# AST1044.net
KiCad netlist of a schematic drawn in EAGLE
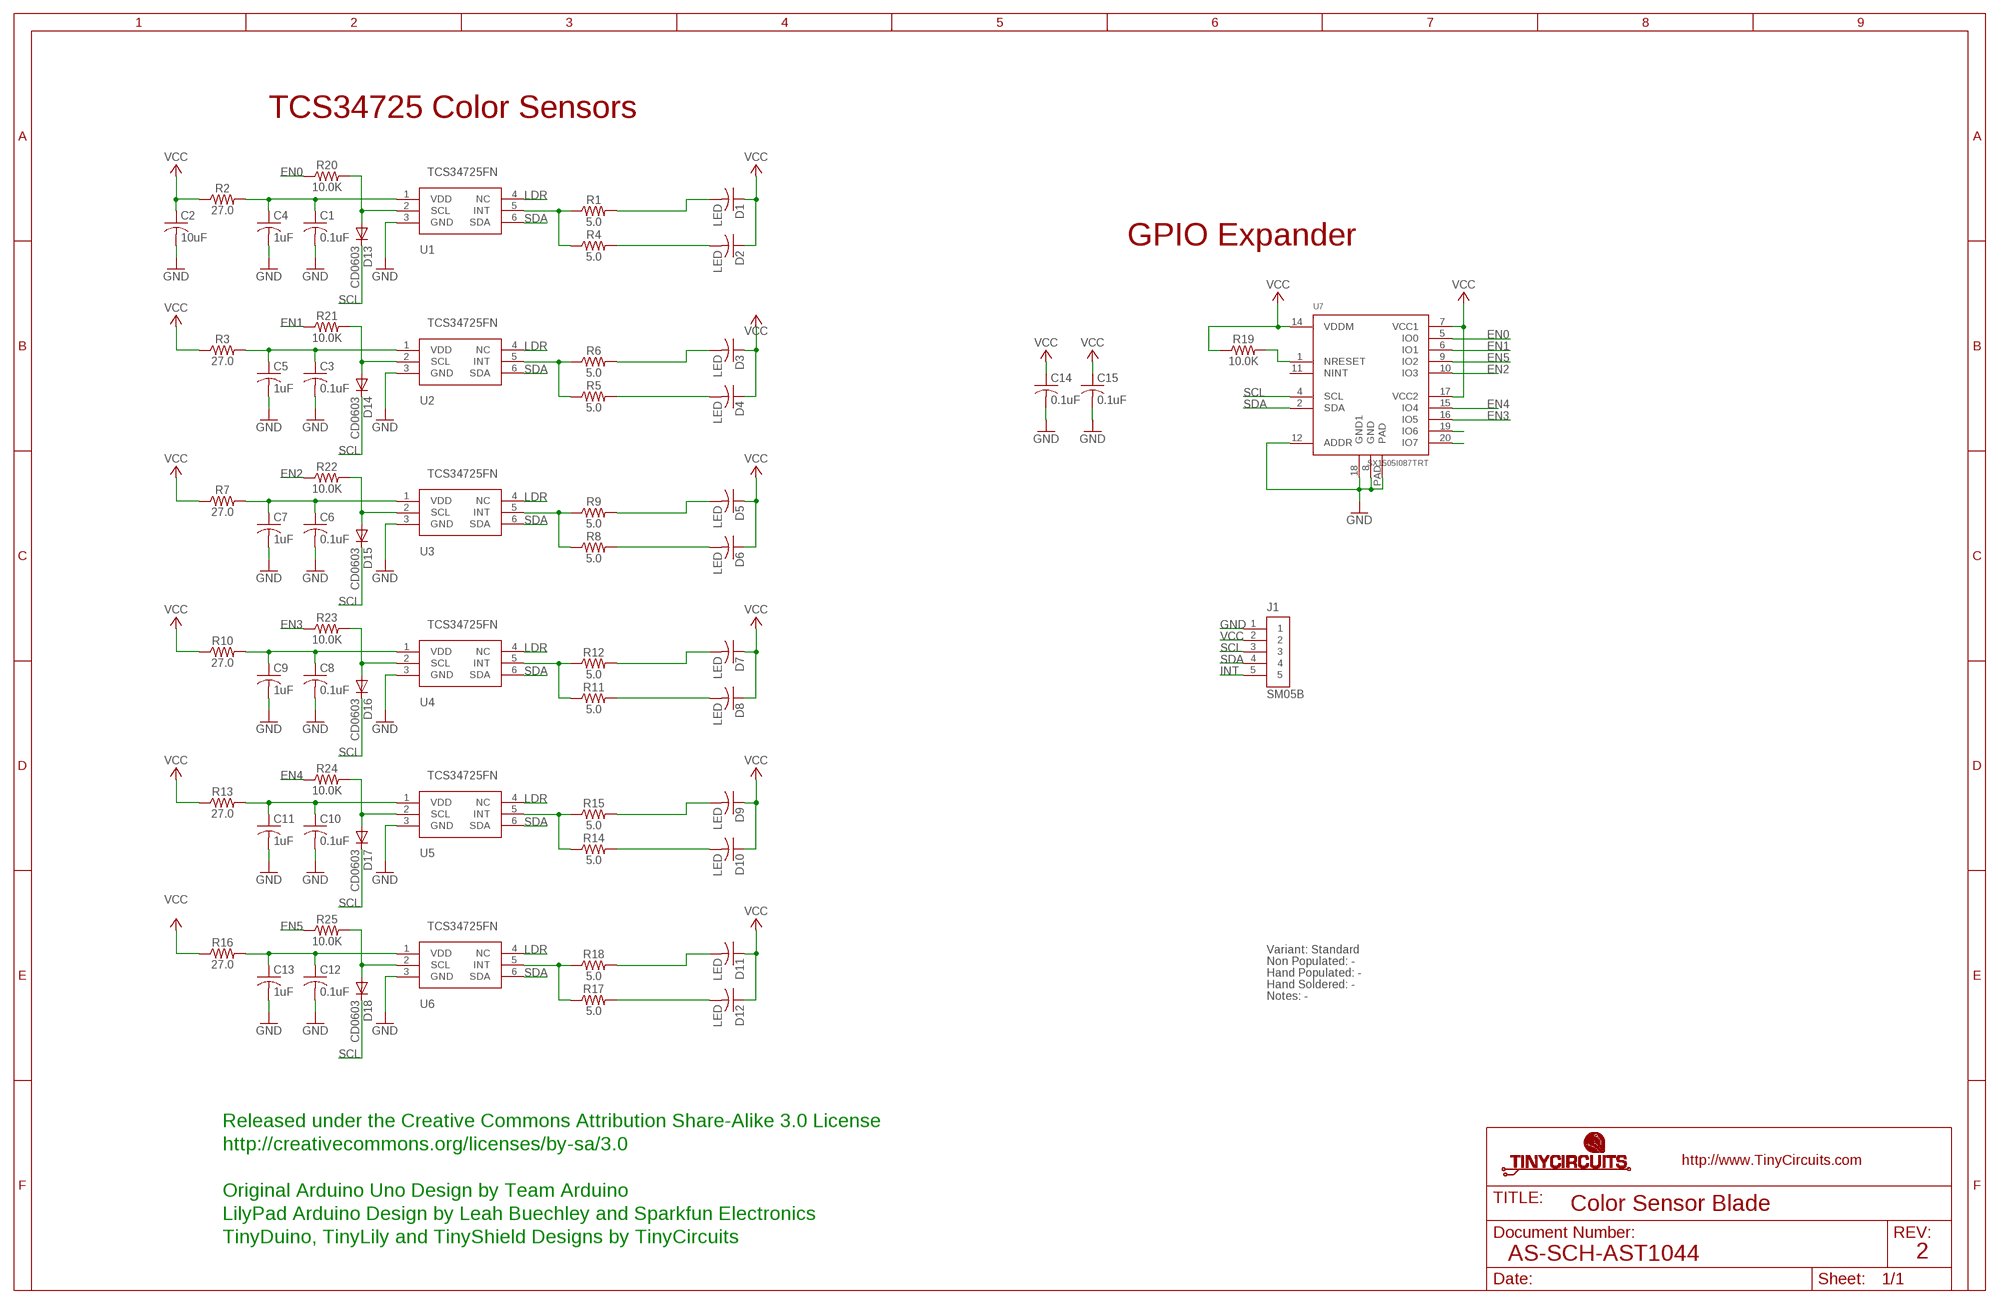
[diagram p0: schematic, sheet 1]

(export (version "E")
  (design (tool "Eeschema 10.0.6"))
  (components
    (comp (ref "C1")
      (value "0.1uF")
      (footprint "eagle-import:C0402")
      (fields (field (name "PARTNO") "AS-ITM-00008"))
      (libsource (lib "eagle-import") (part "AS-ITM-00008"))
    )
    (comp (ref "C2")
      (value "10uF")
      (footprint "eagle-import:C0603")
      (fields (field (name "PARTNO") "AS-ITM-00002"))
      (libsource (lib "eagle-import") (part "AS-ITM-00002"))
    )
    (comp (ref "C3")
      (value "0.1uF")
      (footprint "eagle-import:C0402")
      (fields (field (name "PARTNO") "AS-ITM-00008"))
      (libsource (lib "eagle-import") (part "AS-ITM-00008"))
    )
    (comp (ref "C4")
      (value "1uF")
      (footprint "eagle-import:C0402")
      (fields (field (name "PARTNO") "AS-ITM-00105") (field (name "PARTNO_1") "AS-ITM-00105"))
      (libsource (lib "eagle-import") (part "AS-ITM-00105"))
    )
    (comp (ref "C5")
      (value "1uF")
      (footprint "eagle-import:C0402")
      (fields (field (name "PARTNO") "AS-ITM-00105") (field (name "PARTNO_1") "AS-ITM-00105"))
      (libsource (lib "eagle-import") (part "AS-ITM-00105"))
    )
    (comp (ref "C6")
      (value "0.1uF")
      (footprint "eagle-import:C0402")
      (fields (field (name "PARTNO") "AS-ITM-00008"))
      (libsource (lib "eagle-import") (part "AS-ITM-00008"))
    )
    (comp (ref "C7")
      (value "1uF")
      (footprint "eagle-import:C0402")
      (fields (field (name "PARTNO") "AS-ITM-00105") (field (name "PARTNO_1") "AS-ITM-00105"))
      (libsource (lib "eagle-import") (part "AS-ITM-00105"))
    )
    (comp (ref "C8")
      (value "0.1uF")
      (footprint "eagle-import:C0402")
      (fields (field (name "PARTNO") "AS-ITM-00008"))
      (libsource (lib "eagle-import") (part "AS-ITM-00008"))
    )
    (comp (ref "C9")
      (value "1uF")
      (footprint "eagle-import:C0402")
      (fields (field (name "PARTNO") "AS-ITM-00105") (field (name "PARTNO_1") "AS-ITM-00105"))
      (libsource (lib "eagle-import") (part "AS-ITM-00105"))
    )
    (comp (ref "C10")
      (value "0.1uF")
      (footprint "eagle-import:C0402")
      (fields (field (name "PARTNO") "AS-ITM-00008"))
      (libsource (lib "eagle-import") (part "AS-ITM-00008"))
    )
    (comp (ref "C11")
      (value "1uF")
      (footprint "eagle-import:C0402")
      (fields (field (name "PARTNO") "AS-ITM-00105") (field (name "PARTNO_1") "AS-ITM-00105"))
      (libsource (lib "eagle-import") (part "AS-ITM-00105"))
    )
    (comp (ref "C12")
      (value "0.1uF")
      (footprint "eagle-import:C0402")
      (fields (field (name "PARTNO") "AS-ITM-00008"))
      (libsource (lib "eagle-import") (part "AS-ITM-00008"))
    )
    (comp (ref "C13")
      (value "1uF")
      (footprint "eagle-import:C0402")
      (fields (field (name "PARTNO") "AS-ITM-00105") (field (name "PARTNO_1") "AS-ITM-00105"))
      (libsource (lib "eagle-import") (part "AS-ITM-00105"))
    )
    (comp (ref "C14")
      (value "0.1uF")
      (footprint "eagle-import:C0402")
      (fields (field (name "PARTNO") "AS-ITM-00008"))
      (libsource (lib "eagle-import") (part "AS-ITM-00008"))
    )
    (comp (ref "C15")
      (value "0.1uF")
      (footprint "eagle-import:C0402")
      (fields (field (name "PARTNO") "AS-ITM-00008"))
      (libsource (lib "eagle-import") (part "AS-ITM-00008"))
    )
    (comp (ref "D1")
      (value "LED")
      (footprint "eagle-import:C1206")
      (fields (field (name "PARTNO") "AS-ITM-00049") (field (name "PARTNO_1") "AS-ITM-00049"))
      (libsource (lib "eagle-import") (part "AS-ITM-00049"))
    )
    (comp (ref "D2")
      (value "LED")
      (footprint "eagle-import:C1206")
      (fields (field (name "PARTNO") "AS-ITM-00049") (field (name "PARTNO_1") "AS-ITM-00049"))
      (libsource (lib "eagle-import") (part "AS-ITM-00049"))
    )
    (comp (ref "D3")
      (value "LED")
      (footprint "eagle-import:C1206")
      (fields (field (name "PARTNO") "AS-ITM-00049") (field (name "PARTNO_1") "AS-ITM-00049"))
      (libsource (lib "eagle-import") (part "AS-ITM-00049"))
    )
    (comp (ref "D4")
      (value "LED")
      (footprint "eagle-import:C1206")
      (fields (field (name "PARTNO") "AS-ITM-00049") (field (name "PARTNO_1") "AS-ITM-00049"))
      (libsource (lib "eagle-import") (part "AS-ITM-00049"))
    )
    (comp (ref "D5")
      (value "LED")
      (footprint "eagle-import:C1206")
      (fields (field (name "PARTNO") "AS-ITM-00049") (field (name "PARTNO_1") "AS-ITM-00049"))
      (libsource (lib "eagle-import") (part "AS-ITM-00049"))
    )
    (comp (ref "D6")
      (value "LED")
      (footprint "eagle-import:C1206")
      (fields (field (name "PARTNO") "AS-ITM-00049") (field (name "PARTNO_1") "AS-ITM-00049"))
      (libsource (lib "eagle-import") (part "AS-ITM-00049"))
    )
    (comp (ref "D7")
      (value "LED")
      (footprint "eagle-import:C1206")
      (fields (field (name "PARTNO") "AS-ITM-00049") (field (name "PARTNO_1") "AS-ITM-00049"))
      (libsource (lib "eagle-import") (part "AS-ITM-00049"))
    )
    (comp (ref "D8")
      (value "LED")
      (footprint "eagle-import:C1206")
      (fields (field (name "PARTNO") "AS-ITM-00049") (field (name "PARTNO_1") "AS-ITM-00049"))
      (libsource (lib "eagle-import") (part "AS-ITM-00049"))
    )
    (comp (ref "D9")
      (value "LED")
      (footprint "eagle-import:C1206")
      (fields (field (name "PARTNO") "AS-ITM-00049") (field (name "PARTNO_1") "AS-ITM-00049"))
      (libsource (lib "eagle-import") (part "AS-ITM-00049"))
    )
    (comp (ref "D10")
      (value "LED")
      (footprint "eagle-import:C1206")
      (fields (field (name "PARTNO") "AS-ITM-00049") (field (name "PARTNO_1") "AS-ITM-00049"))
      (libsource (lib "eagle-import") (part "AS-ITM-00049"))
    )
    (comp (ref "D11")
      (value "LED")
      (footprint "eagle-import:C1206")
      (fields (field (name "PARTNO") "AS-ITM-00049") (field (name "PARTNO_1") "AS-ITM-00049"))
      (libsource (lib "eagle-import") (part "AS-ITM-00049"))
    )
    (comp (ref "D12")
      (value "LED")
      (footprint "eagle-import:C1206")
      (fields (field (name "PARTNO") "AS-ITM-00049") (field (name "PARTNO_1") "AS-ITM-00049"))
      (libsource (lib "eagle-import") (part "AS-ITM-00049"))
    )
    (comp (ref "D13")
      (value "CD0603")
      (footprint "eagle-import:0603")
      (fields (field (name "PARTNO") "AS-ITM-00009"))
      (libsource (lib "eagle-import") (part "AS-ITM-00009"))
    )
    (comp (ref "D14")
      (value "CD0603")
      (footprint "eagle-import:0603")
      (fields (field (name "PARTNO") "AS-ITM-00009"))
      (libsource (lib "eagle-import") (part "AS-ITM-00009"))
    )
    (comp (ref "D15")
      (value "CD0603")
      (footprint "eagle-import:0603")
      (fields (field (name "PARTNO") "AS-ITM-00009"))
      (libsource (lib "eagle-import") (part "AS-ITM-00009"))
    )
    (comp (ref "D16")
      (value "CD0603")
      (footprint "eagle-import:0603")
      (fields (field (name "PARTNO") "AS-ITM-00009"))
      (libsource (lib "eagle-import") (part "AS-ITM-00009"))
    )
    (comp (ref "D17")
      (value "CD0603")
      (footprint "eagle-import:0603")
      (fields (field (name "PARTNO") "AS-ITM-00009"))
      (libsource (lib "eagle-import") (part "AS-ITM-00009"))
    )
    (comp (ref "D18")
      (value "CD0603")
      (footprint "eagle-import:0603")
      (fields (field (name "PARTNO") "AS-ITM-00009"))
      (libsource (lib "eagle-import") (part "AS-ITM-00009"))
    )
    (comp (ref "J1")
      (value "SM05B")
      (footprint "eagle-import:JST_SH_5X1_EDGE")
      (fields (field (name "PARTNO") "AS-ITM-00340"))
      (libsource (lib "eagle-import") (part "AS-ITM-00340EDGE"))
    )
    (comp (ref "R1")
      (value "5.0")
      (footprint "eagle-import:0402")
      (fields (field (name "PARTNO") "AS-ITM-00289") (field (name "PARTNO_1") "AS-ITM-00289"))
      (libsource (lib "eagle-import") (part "AS-ITM-00289"))
    )
    (comp (ref "R2")
      (value "27.0")
      (footprint "eagle-import:0402")
      (fields (field (name "PARTNO") "AS-ITM-00240"))
      (libsource (lib "eagle-import") (part "AS-ITM-00240"))
    )
    (comp (ref "R3")
      (value "27.0")
      (footprint "eagle-import:0402")
      (fields (field (name "PARTNO") "AS-ITM-00240"))
      (libsource (lib "eagle-import") (part "AS-ITM-00240"))
    )
    (comp (ref "R4")
      (value "5.0")
      (footprint "eagle-import:0402")
      (fields (field (name "PARTNO") "AS-ITM-00289") (field (name "PARTNO_1") "AS-ITM-00289"))
      (libsource (lib "eagle-import") (part "AS-ITM-00289"))
    )
    (comp (ref "R5")
      (value "5.0")
      (footprint "eagle-import:0402")
      (fields (field (name "PARTNO") "AS-ITM-00289") (field (name "PARTNO_1") "AS-ITM-00289"))
      (libsource (lib "eagle-import") (part "AS-ITM-00289"))
    )
    (comp (ref "R6")
      (value "5.0")
      (footprint "eagle-import:0402")
      (fields (field (name "PARTNO") "AS-ITM-00289") (field (name "PARTNO_1") "AS-ITM-00289"))
      (libsource (lib "eagle-import") (part "AS-ITM-00289"))
    )
    (comp (ref "R7")
      (value "27.0")
      (footprint "eagle-import:0402")
      (fields (field (name "PARTNO") "AS-ITM-00240"))
      (libsource (lib "eagle-import") (part "AS-ITM-00240"))
    )
    (comp (ref "R8")
      (value "5.0")
      (footprint "eagle-import:0402")
      (fields (field (name "PARTNO") "AS-ITM-00289") (field (name "PARTNO_1") "AS-ITM-00289"))
      (libsource (lib "eagle-import") (part "AS-ITM-00289"))
    )
    (comp (ref "R9")
      (value "5.0")
      (footprint "eagle-import:0402")
      (fields (field (name "PARTNO") "AS-ITM-00289") (field (name "PARTNO_1") "AS-ITM-00289"))
      (libsource (lib "eagle-import") (part "AS-ITM-00289"))
    )
    (comp (ref "R10")
      (value "27.0")
      (footprint "eagle-import:0402")
      (fields (field (name "PARTNO") "AS-ITM-00240"))
      (libsource (lib "eagle-import") (part "AS-ITM-00240"))
    )
    (comp (ref "R11")
      (value "5.0")
      (footprint "eagle-import:0402")
      (fields (field (name "PARTNO") "AS-ITM-00289") (field (name "PARTNO_1") "AS-ITM-00289"))
      (libsource (lib "eagle-import") (part "AS-ITM-00289"))
    )
    (comp (ref "R12")
      (value "5.0")
      (footprint "eagle-import:0402")
      (fields (field (name "PARTNO") "AS-ITM-00289") (field (name "PARTNO_1") "AS-ITM-00289"))
      (libsource (lib "eagle-import") (part "AS-ITM-00289"))
    )
    (comp (ref "R13")
      (value "27.0")
      (footprint "eagle-import:0402")
      (fields (field (name "PARTNO") "AS-ITM-00240"))
      (libsource (lib "eagle-import") (part "AS-ITM-00240"))
    )
    (comp (ref "R14")
      (value "5.0")
      (footprint "eagle-import:0402")
      (fields (field (name "PARTNO") "AS-ITM-00289") (field (name "PARTNO_1") "AS-ITM-00289"))
      (libsource (lib "eagle-import") (part "AS-ITM-00289"))
    )
    (comp (ref "R15")
      (value "5.0")
      (footprint "eagle-import:0402")
      (fields (field (name "PARTNO") "AS-ITM-00289") (field (name "PARTNO_1") "AS-ITM-00289"))
      (libsource (lib "eagle-import") (part "AS-ITM-00289"))
    )
    (comp (ref "R16")
      (value "27.0")
      (footprint "eagle-import:0402")
      (fields (field (name "PARTNO") "AS-ITM-00240"))
      (libsource (lib "eagle-import") (part "AS-ITM-00240"))
    )
    (comp (ref "R17")
      (value "5.0")
      (footprint "eagle-import:0402")
      (fields (field (name "PARTNO") "AS-ITM-00289") (field (name "PARTNO_1") "AS-ITM-00289"))
      (libsource (lib "eagle-import") (part "AS-ITM-00289"))
    )
    (comp (ref "R18")
      (value "5.0")
      (footprint "eagle-import:0402")
      (fields (field (name "PARTNO") "AS-ITM-00289") (field (name "PARTNO_1") "AS-ITM-00289"))
      (libsource (lib "eagle-import") (part "AS-ITM-00289"))
    )
    (comp (ref "R19")
      (value "10.0K")
      (footprint "eagle-import:0402")
      (fields (field (name "PARTNO") "AS-ITM-00032"))
      (libsource (lib "eagle-import") (part "AS-ITM-00032"))
    )
    (comp (ref "R20")
      (value "10.0K")
      (footprint "eagle-import:0402")
      (fields (field (name "PARTNO") "AS-ITM-00032"))
      (libsource (lib "eagle-import") (part "AS-ITM-00032"))
    )
    (comp (ref "R21")
      (value "10.0K")
      (footprint "eagle-import:0402")
      (fields (field (name "PARTNO") "AS-ITM-00032"))
      (libsource (lib "eagle-import") (part "AS-ITM-00032"))
    )
    (comp (ref "R22")
      (value "10.0K")
      (footprint "eagle-import:0402")
      (fields (field (name "PARTNO") "AS-ITM-00032"))
      (libsource (lib "eagle-import") (part "AS-ITM-00032"))
    )
    (comp (ref "R23")
      (value "10.0K")
      (footprint "eagle-import:0402")
      (fields (field (name "PARTNO") "AS-ITM-00032"))
      (libsource (lib "eagle-import") (part "AS-ITM-00032"))
    )
    (comp (ref "R24")
      (value "10.0K")
      (footprint "eagle-import:0402")
      (fields (field (name "PARTNO") "AS-ITM-00032"))
      (libsource (lib "eagle-import") (part "AS-ITM-00032"))
    )
    (comp (ref "R25")
      (value "10.0K")
      (footprint "eagle-import:0402")
      (fields (field (name "PARTNO") "AS-ITM-00032"))
      (libsource (lib "eagle-import") (part "AS-ITM-00032"))
    )
    (comp (ref "U1")
      (value "TCS34725FN")
      (footprint "eagle-import:TSL2572")
      (fields (field (name "PARTNO") "AS-ITM-00140") (field (name "PARTNO_1") "AS-ITM-00140"))
      (libsource (lib "eagle-import") (part "AS-ITM-00140"))
    )
    (comp (ref "U2")
      (value "TCS34725FN")
      (footprint "eagle-import:TSL2572")
      (fields (field (name "PARTNO") "AS-ITM-00140") (field (name "PARTNO_1") "AS-ITM-00140"))
      (libsource (lib "eagle-import") (part "AS-ITM-00140"))
    )
    (comp (ref "U3")
      (value "TCS34725FN")
      (footprint "eagle-import:TSL2572")
      (fields (field (name "PARTNO") "AS-ITM-00140") (field (name "PARTNO_1") "AS-ITM-00140"))
      (libsource (lib "eagle-import") (part "AS-ITM-00140"))
    )
    (comp (ref "U4")
      (value "TCS34725FN")
      (footprint "eagle-import:TSL2572")
      (fields (field (name "PARTNO") "AS-ITM-00140") (field (name "PARTNO_1") "AS-ITM-00140"))
      (libsource (lib "eagle-import") (part "AS-ITM-00140"))
    )
    (comp (ref "U5")
      (value "TCS34725FN")
      (footprint "eagle-import:TSL2572")
      (fields (field (name "PARTNO") "AS-ITM-00140") (field (name "PARTNO_1") "AS-ITM-00140"))
      (libsource (lib "eagle-import") (part "AS-ITM-00140"))
    )
    (comp (ref "U6")
      (value "TCS34725FN")
      (footprint "eagle-import:TSL2572")
      (fields (field (name "PARTNO") "AS-ITM-00140") (field (name "PARTNO_1") "AS-ITM-00140"))
      (libsource (lib "eagle-import") (part "AS-ITM-00140"))
    )
    (comp (ref "U7")
      (value "SX1505I087TRT")
      (footprint "eagle-import:QFN-UT20")
      (fields (field (name "PARTNO") "AS-ITM-00203"))
      (libsource (lib "eagle-import") (part "AS-ITM-00203"))
    )
  )
  (nets
    (net (code "1") (name "/EN0") (class "Default")
      (node (ref "R20") (pin "1") (pinfunction "1_1") (pintype "passive"))
      (node (ref "U7") (pin "5") (pinfunction "IO0_5") (pintype "bidirectional"))
    )
    (net (code "2") (name "/EN1") (class "Default")
      (node (ref "R21") (pin "1") (pinfunction "1_1") (pintype "passive"))
      (node (ref "U7") (pin "6") (pinfunction "IO1_6") (pintype "bidirectional"))
    )
    (net (code "3") (name "/EN2") (class "Default")
      (node (ref "R22") (pin "1") (pinfunction "1_1") (pintype "passive"))
      (node (ref "U7") (pin "10") (pinfunction "IO3_10") (pintype "bidirectional"))
    )
    (net (code "4") (name "/EN3") (class "Default")
      (node (ref "R23") (pin "1") (pinfunction "1_1") (pintype "passive"))
      (node (ref "U7") (pin "16") (pinfunction "IO5_16") (pintype "bidirectional"))
    )
    (net (code "5") (name "/EN4") (class "Default")
      (node (ref "R24") (pin "1") (pinfunction "1_1") (pintype "passive"))
      (node (ref "U7") (pin "15") (pinfunction "IO4_15") (pintype "bidirectional"))
    )
    (net (code "6") (name "/EN5") (class "Default")
      (node (ref "R25") (pin "1") (pinfunction "1_1") (pintype "passive"))
      (node (ref "U7") (pin "9") (pinfunction "IO2_9") (pintype "bidirectional"))
    )
    (net (code "7") (name "/INT") (class "Default")
      (node (ref "J1") (pin "5") (pinfunction "5_5") (pintype "bidirectional"))
    )
    (net (code "8") (name "/LDR") (class "Default")
      (node (ref "U1") (pin "4") (pinfunction "NC_4") (pintype "bidirectional"))
      (node (ref "U2") (pin "4") (pinfunction "NC_4") (pintype "bidirectional"))
      (node (ref "U3") (pin "4") (pinfunction "NC_4") (pintype "bidirectional"))
      (node (ref "U4") (pin "4") (pinfunction "NC_4") (pintype "bidirectional"))
      (node (ref "U5") (pin "4") (pinfunction "NC_4") (pintype "bidirectional"))
      (node (ref "U6") (pin "4") (pinfunction "NC_4") (pintype "bidirectional"))
    )
    (net (code "9") (name "/SCL") (class "Default")
      (node (ref "D13") (pin "C") (pinfunction "C_C") (pintype "passive"))
      (node (ref "D14") (pin "C") (pinfunction "C_C") (pintype "passive"))
      (node (ref "D15") (pin "C") (pinfunction "C_C") (pintype "passive"))
      (node (ref "D16") (pin "C") (pinfunction "C_C") (pintype "passive"))
      (node (ref "D17") (pin "C") (pinfunction "C_C") (pintype "passive"))
      (node (ref "D18") (pin "C") (pinfunction "C_C") (pintype "passive"))
      (node (ref "J1") (pin "3") (pinfunction "3_3") (pintype "bidirectional"))
      (node (ref "U7") (pin "4") (pinfunction "SCL_4") (pintype "bidirectional"))
    )
    (net (code "10") (name "/SDA") (class "Default")
      (node (ref "J1") (pin "4") (pinfunction "4_4") (pintype "bidirectional"))
      (node (ref "U1") (pin "6") (pinfunction "SDA_6") (pintype "bidirectional"))
      (node (ref "U2") (pin "6") (pinfunction "SDA_6") (pintype "bidirectional"))
      (node (ref "U3") (pin "6") (pinfunction "SDA_6") (pintype "bidirectional"))
      (node (ref "U4") (pin "6") (pinfunction "SDA_6") (pintype "bidirectional"))
      (node (ref "U5") (pin "6") (pinfunction "SDA_6") (pintype "bidirectional"))
      (node (ref "U6") (pin "6") (pinfunction "SDA_6") (pintype "bidirectional"))
      (node (ref "U7") (pin "2") (pinfunction "SDA_2") (pintype "bidirectional"))
    )
    (net (code "11") (name "GND") (class "Default")
      (node (ref "C1") (pin "2") (pinfunction "2_2") (pintype "passive"))
      (node (ref "C10") (pin "2") (pinfunction "2_2") (pintype "passive"))
      (node (ref "C11") (pin "2") (pinfunction "2_2") (pintype "passive"))
      (node (ref "C12") (pin "2") (pinfunction "2_2") (pintype "passive"))
      (node (ref "C13") (pin "2") (pinfunction "2_2") (pintype "passive"))
      (node (ref "C14") (pin "2") (pinfunction "2_2") (pintype "passive"))
      (node (ref "C15") (pin "2") (pinfunction "2_2") (pintype "passive"))
      (node (ref "C2") (pin "2") (pinfunction "2_2") (pintype "passive"))
      (node (ref "C3") (pin "2") (pinfunction "2_2") (pintype "passive"))
      (node (ref "C4") (pin "2") (pinfunction "2_2") (pintype "passive"))
      (node (ref "C5") (pin "2") (pinfunction "2_2") (pintype "passive"))
      (node (ref "C6") (pin "2") (pinfunction "2_2") (pintype "passive"))
      (node (ref "C7") (pin "2") (pinfunction "2_2") (pintype "passive"))
      (node (ref "C8") (pin "2") (pinfunction "2_2") (pintype "passive"))
      (node (ref "C9") (pin "2") (pinfunction "2_2") (pintype "passive"))
      (node (ref "J1") (pin "1") (pinfunction "1_1") (pintype "bidirectional"))
      (node (ref "U1") (pin "3") (pinfunction "GND_3") (pintype "bidirectional"))
      (node (ref "U2") (pin "3") (pinfunction "GND_3") (pintype "bidirectional"))
      (node (ref "U3") (pin "3") (pinfunction "GND_3") (pintype "bidirectional"))
      (node (ref "U4") (pin "3") (pinfunction "GND_3") (pintype "bidirectional"))
      (node (ref "U5") (pin "3") (pinfunction "GND_3") (pintype "bidirectional"))
      (node (ref "U6") (pin "3") (pinfunction "GND_3") (pintype "bidirectional"))
      (node (ref "U7") (pin "12") (pinfunction "ADDR_12") (pintype "bidirectional"))
      (node (ref "U7") (pin "18") (pinfunction "GND1_18") (pintype "bidirectional"))
      (node (ref "U7") (pin "8") (pinfunction "GND_8") (pintype "bidirectional"))
      (node (ref "U7") (pin "PAD") (pinfunction "PAD_PAD") (pintype "bidirectional"))
    )
    (net (code "12") (name "Net-(D1-Pad2)") (class "Default")
      (node (ref "D1") (pin "2") (pinfunction "2_2") (pintype "passive"))
      (node (ref "R1") (pin "2") (pinfunction "2_2") (pintype "passive"))
    )
    (net (code "13") (name "Net-(D2-Pad2)") (class "Default")
      (node (ref "D2") (pin "2") (pinfunction "2_2") (pintype "passive"))
      (node (ref "R4") (pin "2") (pinfunction "2_2") (pintype "passive"))
    )
    (net (code "14") (name "Net-(D3-Pad2)") (class "Default")
      (node (ref "D3") (pin "2") (pinfunction "2_2") (pintype "passive"))
      (node (ref "R6") (pin "2") (pinfunction "2_2") (pintype "passive"))
    )
    (net (code "15") (name "Net-(D4-Pad2)") (class "Default")
      (node (ref "D4") (pin "2") (pinfunction "2_2") (pintype "passive"))
      (node (ref "R5") (pin "2") (pinfunction "2_2") (pintype "passive"))
    )
    (net (code "16") (name "Net-(D5-Pad2)") (class "Default")
      (node (ref "D5") (pin "2") (pinfunction "2_2") (pintype "passive"))
      (node (ref "R9") (pin "2") (pinfunction "2_2") (pintype "passive"))
    )
    (net (code "17") (name "Net-(D6-Pad2)") (class "Default")
      (node (ref "D6") (pin "2") (pinfunction "2_2") (pintype "passive"))
      (node (ref "R8") (pin "2") (pinfunction "2_2") (pintype "passive"))
    )
    (net (code "18") (name "Net-(D7-Pad2)") (class "Default")
      (node (ref "D7") (pin "2") (pinfunction "2_2") (pintype "passive"))
      (node (ref "R12") (pin "2") (pinfunction "2_2") (pintype "passive"))
    )
    (net (code "19") (name "Net-(D8-Pad2)") (class "Default")
      (node (ref "D8") (pin "2") (pinfunction "2_2") (pintype "passive"))
      (node (ref "R11") (pin "2") (pinfunction "2_2") (pintype "passive"))
    )
    (net (code "20") (name "Net-(D9-Pad2)") (class "Default")
      (node (ref "D9") (pin "2") (pinfunction "2_2") (pintype "passive"))
      (node (ref "R15") (pin "2") (pinfunction "2_2") (pintype "passive"))
    )
    (net (code "21") (name "Net-(D10-Pad2)") (class "Default")
      (node (ref "D10") (pin "2") (pinfunction "2_2") (pintype "passive"))
      (node (ref "R14") (pin "2") (pinfunction "2_2") (pintype "passive"))
    )
    (net (code "22") (name "Net-(D11-Pad2)") (class "Default")
      (node (ref "D11") (pin "2") (pinfunction "2_2") (pintype "passive"))
      (node (ref "R18") (pin "2") (pinfunction "2_2") (pintype "passive"))
    )
    (net (code "23") (name "Net-(D12-Pad2)") (class "Default")
      (node (ref "D12") (pin "2") (pinfunction "2_2") (pintype "passive"))
      (node (ref "R17") (pin "2") (pinfunction "2_2") (pintype "passive"))
    )
    (net (code "24") (name "Net-(U1-INT)") (class "Default")
      (node (ref "R1") (pin "1") (pinfunction "1_1") (pintype "passive"))
      (node (ref "R4") (pin "1") (pinfunction "1_1") (pintype "passive"))
      (node (ref "U1") (pin "5") (pinfunction "INT_5") (pintype "bidirectional"))
    )
    (net (code "25") (name "Net-(U1-SCL)") (class "Default")
      (node (ref "D13") (pin "A") (pinfunction "A_A") (pintype "passive"))
      (node (ref "R20") (pin "2") (pinfunction "2_2") (pintype "passive"))
      (node (ref "U1") (pin "2") (pinfunction "SCL_2") (pintype "bidirectional"))
    )
    (net (code "26") (name "Net-(U1-VDD)") (class "Default")
      (node (ref "C1") (pin "1") (pinfunction "1_1") (pintype "passive"))
      (node (ref "C4") (pin "1") (pinfunction "1_1") (pintype "passive"))
      (node (ref "R2") (pin "2") (pinfunction "2_2") (pintype "passive"))
      (node (ref "U1") (pin "1") (pinfunction "VDD_1") (pintype "bidirectional"))
    )
    (net (code "27") (name "Net-(U2-INT)") (class "Default")
      (node (ref "R5") (pin "1") (pinfunction "1_1") (pintype "passive"))
      (node (ref "R6") (pin "1") (pinfunction "1_1") (pintype "passive"))
      (node (ref "U2") (pin "5") (pinfunction "INT_5") (pintype "bidirectional"))
    )
    (net (code "28") (name "Net-(U2-SCL)") (class "Default")
      (node (ref "D14") (pin "A") (pinfunction "A_A") (pintype "passive"))
      (node (ref "R21") (pin "2") (pinfunction "2_2") (pintype "passive"))
      (node (ref "U2") (pin "2") (pinfunction "SCL_2") (pintype "bidirectional"))
    )
    (net (code "29") (name "Net-(U2-VDD)") (class "Default")
      (node (ref "C3") (pin "1") (pinfunction "1_1") (pintype "passive"))
      (node (ref "C5") (pin "1") (pinfunction "1_1") (pintype "passive"))
      (node (ref "R3") (pin "2") (pinfunction "2_2") (pintype "passive"))
      (node (ref "U2") (pin "1") (pinfunction "VDD_1") (pintype "bidirectional"))
    )
    (net (code "30") (name "Net-(U3-INT)") (class "Default")
      (node (ref "R8") (pin "1") (pinfunction "1_1") (pintype "passive"))
      (node (ref "R9") (pin "1") (pinfunction "1_1") (pintype "passive"))
      (node (ref "U3") (pin "5") (pinfunction "INT_5") (pintype "bidirectional"))
    )
    (net (code "31") (name "Net-(U3-SCL)") (class "Default")
      (node (ref "D15") (pin "A") (pinfunction "A_A") (pintype "passive"))
      (node (ref "R22") (pin "2") (pinfunction "2_2") (pintype "passive"))
      (node (ref "U3") (pin "2") (pinfunction "SCL_2") (pintype "bidirectional"))
    )
    (net (code "32") (name "Net-(U3-VDD)") (class "Default")
      (node (ref "C6") (pin "1") (pinfunction "1_1") (pintype "passive"))
      (node (ref "C7") (pin "1") (pinfunction "1_1") (pintype "passive"))
      (node (ref "R7") (pin "2") (pinfunction "2_2") (pintype "passive"))
      (node (ref "U3") (pin "1") (pinfunction "VDD_1") (pintype "bidirectional"))
    )
    (net (code "33") (name "Net-(U4-INT)") (class "Default")
      (node (ref "R11") (pin "1") (pinfunction "1_1") (pintype "passive"))
      (node (ref "R12") (pin "1") (pinfunction "1_1") (pintype "passive"))
      (node (ref "U4") (pin "5") (pinfunction "INT_5") (pintype "bidirectional"))
    )
    (net (code "34") (name "Net-(U4-SCL)") (class "Default")
      (node (ref "D16") (pin "A") (pinfunction "A_A") (pintype "passive"))
      (node (ref "R23") (pin "2") (pinfunction "2_2") (pintype "passive"))
      (node (ref "U4") (pin "2") (pinfunction "SCL_2") (pintype "bidirectional"))
    )
    (net (code "35") (name "Net-(U4-VDD)") (class "Default")
      (node (ref "C8") (pin "1") (pinfunction "1_1") (pintype "passive"))
      (node (ref "C9") (pin "1") (pinfunction "1_1") (pintype "passive"))
      (node (ref "R10") (pin "2") (pinfunction "2_2") (pintype "passive"))
      (node (ref "U4") (pin "1") (pinfunction "VDD_1") (pintype "bidirectional"))
    )
    (net (code "36") (name "Net-(U5-INT)") (class "Default")
      (node (ref "R14") (pin "1") (pinfunction "1_1") (pintype "passive"))
      (node (ref "R15") (pin "1") (pinfunction "1_1") (pintype "passive"))
      (node (ref "U5") (pin "5") (pinfunction "INT_5") (pintype "bidirectional"))
    )
    (net (code "37") (name "Net-(U5-SCL)") (class "Default")
      (node (ref "D17") (pin "A") (pinfunction "A_A") (pintype "passive"))
      (node (ref "R24") (pin "2") (pinfunction "2_2") (pintype "passive"))
      (node (ref "U5") (pin "2") (pinfunction "SCL_2") (pintype "bidirectional"))
    )
    (net (code "38") (name "Net-(U5-VDD)") (class "Default")
      (node (ref "C10") (pin "1") (pinfunction "1_1") (pintype "passive"))
      (node (ref "C11") (pin "1") (pinfunction "1_1") (pintype "passive"))
      (node (ref "R13") (pin "2") (pinfunction "2_2") (pintype "passive"))
      (node (ref "U5") (pin "1") (pinfunction "VDD_1") (pintype "bidirectional"))
    )
    (net (code "39") (name "Net-(U6-INT)") (class "Default")
      (node (ref "R17") (pin "1") (pinfunction "1_1") (pintype "passive"))
      (node (ref "R18") (pin "1") (pinfunction "1_1") (pintype "passive"))
      (node (ref "U6") (pin "5") (pinfunction "INT_5") (pintype "bidirectional"))
    )
    (net (code "40") (name "Net-(U6-SCL)") (class "Default")
      (node (ref "D18") (pin "A") (pinfunction "A_A") (pintype "passive"))
      (node (ref "R25") (pin "2") (pinfunction "2_2") (pintype "passive"))
      (node (ref "U6") (pin "2") (pinfunction "SCL_2") (pintype "bidirectional"))
    )
    (net (code "41") (name "Net-(U6-VDD)") (class "Default")
      (node (ref "C12") (pin "1") (pinfunction "1_1") (pintype "passive"))
      (node (ref "C13") (pin "1") (pinfunction "1_1") (pintype "passive"))
      (node (ref "R16") (pin "2") (pinfunction "2_2") (pintype "passive"))
      (node (ref "U6") (pin "1") (pinfunction "VDD_1") (pintype "bidirectional"))
    )
    (net (code "42") (name "Net-(U7-NRESET)") (class "Default")
      (node (ref "R19") (pin "2") (pinfunction "2_2") (pintype "passive"))
      (node (ref "U7") (pin "1") (pinfunction "NRESET_1") (pintype "bidirectional"))
    )
    (net (code "43") (name "VCC") (class "Default")
      (node (ref "C14") (pin "1") (pinfunction "1_1") (pintype "passive"))
      (node (ref "C15") (pin "1") (pinfunction "1_1") (pintype "passive"))
      (node (ref "C2") (pin "1") (pinfunction "1_1") (pintype "passive"))
      (node (ref "D1") (pin "1") (pinfunction "1_1") (pintype "passive"))
      (node (ref "D10") (pin "1") (pinfunction "1_1") (pintype "passive"))
      (node (ref "D11") (pin "1") (pinfunction "1_1") (pintype "passive"))
      (node (ref "D12") (pin "1") (pinfunction "1_1") (pintype "passive"))
      (node (ref "D2") (pin "1") (pinfunction "1_1") (pintype "passive"))
      (node (ref "D3") (pin "1") (pinfunction "1_1") (pintype "passive"))
      (node (ref "D4") (pin "1") (pinfunction "1_1") (pintype "passive"))
      (node (ref "D5") (pin "1") (pinfunction "1_1") (pintype "passive"))
      (node (ref "D6") (pin "1") (pinfunction "1_1") (pintype "passive"))
      (node (ref "D7") (pin "1") (pinfunction "1_1") (pintype "passive"))
      (node (ref "D8") (pin "1") (pinfunction "1_1") (pintype "passive"))
      (node (ref "D9") (pin "1") (pinfunction "1_1") (pintype "passive"))
      (node (ref "J1") (pin "2") (pinfunction "2_2") (pintype "bidirectional"))
      (node (ref "R10") (pin "1") (pinfunction "1_1") (pintype "passive"))
      (node (ref "R13") (pin "1") (pinfunction "1_1") (pintype "passive"))
      (node (ref "R16") (pin "1") (pinfunction "1_1") (pintype "passive"))
      (node (ref "R19") (pin "1") (pinfunction "1_1") (pintype "passive"))
      (node (ref "R2") (pin "1") (pinfunction "1_1") (pintype "passive"))
      (node (ref "R3") (pin "1") (pinfunction "1_1") (pintype "passive"))
      (node (ref "R7") (pin "1") (pinfunction "1_1") (pintype "passive"))
      (node (ref "U7") (pin "14") (pinfunction "VDDM_14") (pintype "bidirectional"))
      (node (ref "U7") (pin "17") (pinfunction "VCC2_17") (pintype "bidirectional"))
      (node (ref "U7") (pin "7") (pinfunction "VCC1_7") (pintype "bidirectional"))
    )
    (net (code "44") (name "unconnected-(U7-IO6-Pad19)") (class "Default")
      (node (ref "U7") (pin "19") (pinfunction "IO6_19") (pintype "bidirectional"))
    )
    (net (code "45") (name "unconnected-(U7-IO7-Pad20)") (class "Default")
      (node (ref "U7") (pin "20") (pinfunction "IO7_20") (pintype "bidirectional"))
    )
    (net (code "46") (name "unconnected-(U7-NINT-Pad11)") (class "Default")
      (node (ref "U7") (pin "11") (pinfunction "NINT_11") (pintype "bidirectional"))
    )
  )
)
